# electrical_interface.net
KiCad netlist of a schematic drawn in Altium Designer
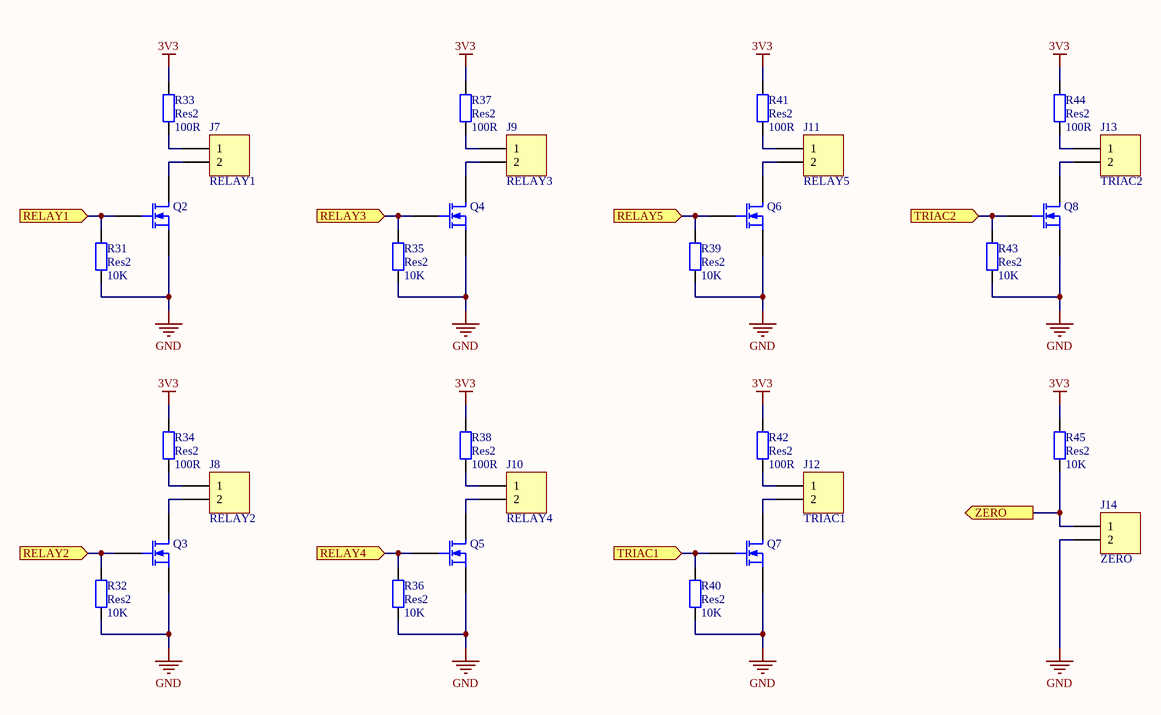
[diagram p0: electrical_interface.SchDoc]

(export (version "E")
  (design (tool "Eeschema 10.0.6"))
  (components
    (comp (ref "J7")
      (value "RELAY1")
      (footprint "Terminal Block")
      (description "Header, 2-Pin")
      (fields (field (name "PUBLISHER") "Altium Limited"))
      (libsource (lib "Miscellaneous Connectors") (part "Header 2"))
    )
    (comp (ref "J8")
      (value "RELAY2")
      (footprint "Terminal Block")
      (description "Header, 2-Pin")
      (fields (field (name "PUBLISHER") "Altium Limited"))
      (libsource (lib "Miscellaneous Connectors") (part "Header 2"))
    )
    (comp (ref "J9")
      (value "RELAY3")
      (footprint "Terminal Block")
      (description "Header, 2-Pin")
      (fields (field (name "PUBLISHER") "Altium Limited"))
      (libsource (lib "Miscellaneous Connectors") (part "Header 2"))
    )
    (comp (ref "J10")
      (value "RELAY4")
      (footprint "Terminal Block")
      (description "Header, 2-Pin")
      (fields (field (name "PUBLISHER") "Altium Limited"))
      (libsource (lib "Miscellaneous Connectors") (part "Header 2"))
    )
    (comp (ref "J11")
      (value "RELAY5")
      (footprint "Terminal Block")
      (description "Header, 2-Pin")
      (fields (field (name "PUBLISHER") "Altium Limited"))
      (libsource (lib "Miscellaneous Connectors") (part "Header 2"))
    )
    (comp (ref "J12")
      (value "TRIAC1")
      (footprint "Terminal Block")
      (description "Header, 2-Pin")
      (fields (field (name "PUBLISHER") "Altium Limited"))
      (libsource (lib "Miscellaneous Connectors") (part "Header 2"))
    )
    (comp (ref "J13")
      (value "TRIAC2")
      (footprint "Terminal Block")
      (description "Header, 2-Pin")
      (fields (field (name "PUBLISHER") "Altium Limited"))
      (libsource (lib "Miscellaneous Connectors") (part "Header 2"))
    )
    (comp (ref "J14")
      (value "ZERO")
      (footprint "Terminal Block")
      (description "Header, 2-Pin")
      (fields (field (name "PUBLISHER") "Altium Limited"))
      (libsource (lib "Miscellaneous Connectors") (part "Header 2"))
    )
    (comp (ref "Q2")
      (value "MOSFET-N")
      (footprint "SOT323")
      (description "N-Channel MOSFET")
      (fields (field (name "PUBLISHER") "Altium Limited"))
      (libsource (lib "Miscellaneous Devices") (part "MOSFET-N"))
    )
    (comp (ref "Q3")
      (value "MOSFET-N")
      (footprint "SOT323")
      (description "N-Channel MOSFET")
      (fields (field (name "PUBLISHER") "Altium Limited"))
      (libsource (lib "Miscellaneous Devices") (part "MOSFET-N"))
    )
    (comp (ref "Q4")
      (value "MOSFET-N")
      (footprint "SOT323")
      (description "N-Channel MOSFET")
      (fields (field (name "PUBLISHER") "Altium Limited"))
      (libsource (lib "Miscellaneous Devices") (part "MOSFET-N"))
    )
    (comp (ref "Q5")
      (value "MOSFET-N")
      (footprint "SOT323")
      (description "N-Channel MOSFET")
      (fields (field (name "PUBLISHER") "Altium Limited"))
      (libsource (lib "Miscellaneous Devices") (part "MOSFET-N"))
    )
    (comp (ref "Q6")
      (value "MOSFET-N")
      (footprint "SOT323")
      (description "N-Channel MOSFET")
      (fields (field (name "PUBLISHER") "Altium Limited"))
      (libsource (lib "Miscellaneous Devices") (part "MOSFET-N"))
    )
    (comp (ref "Q7")
      (value "MOSFET-N")
      (footprint "SOT323")
      (description "N-Channel MOSFET")
      (fields (field (name "PUBLISHER") "Altium Limited"))
      (libsource (lib "Miscellaneous Devices") (part "MOSFET-N"))
    )
    (comp (ref "Q8")
      (value "MOSFET-N")
      (footprint "SOT323")
      (description "N-Channel MOSFET")
      (fields (field (name "PUBLISHER") "Altium Limited"))
      (libsource (lib "Miscellaneous Devices") (part "MOSFET-N"))
    )
    (comp (ref "R31")
      (value "Res2")
      (footprint "0603")
      (description "Resistor")
      (fields (field (name "ALTIUM_VALUE") "10K") (field (name "PUBLISHER") "Altium Limited"))
      (libsource (lib "Miscellaneous Devices") (part "Res2"))
    )
    (comp (ref "R32")
      (value "Res2")
      (footprint "0603")
      (description "Resistor")
      (fields (field (name "ALTIUM_VALUE") "10K") (field (name "PUBLISHER") "Altium Limited"))
      (libsource (lib "Miscellaneous Devices") (part "Res2"))
    )
    (comp (ref "R33")
      (value "Res2")
      (footprint "0603")
      (description "Resistor")
      (fields (field (name "ALTIUM_VALUE") "100R") (field (name "PUBLISHER") "Altium Limited"))
      (libsource (lib "Miscellaneous Devices") (part "Res2"))
    )
    (comp (ref "R34")
      (value "Res2")
      (footprint "0603")
      (description "Resistor")
      (fields (field (name "ALTIUM_VALUE") "100R") (field (name "PUBLISHER") "Altium Limited"))
      (libsource (lib "Miscellaneous Devices") (part "Res2"))
    )
    (comp (ref "R35")
      (value "Res2")
      (footprint "0603")
      (description "Resistor")
      (fields (field (name "ALTIUM_VALUE") "10K") (field (name "PUBLISHER") "Altium Limited"))
      (libsource (lib "Miscellaneous Devices") (part "Res2"))
    )
    (comp (ref "R36")
      (value "Res2")
      (footprint "0603")
      (description "Resistor")
      (fields (field (name "ALTIUM_VALUE") "10K") (field (name "PUBLISHER") "Altium Limited"))
      (libsource (lib "Miscellaneous Devices") (part "Res2"))
    )
    (comp (ref "R37")
      (value "Res2")
      (footprint "0603")
      (description "Resistor")
      (fields (field (name "ALTIUM_VALUE") "100R") (field (name "PUBLISHER") "Altium Limited"))
      (libsource (lib "Miscellaneous Devices") (part "Res2"))
    )
    (comp (ref "R38")
      (value "Res2")
      (footprint "0603")
      (description "Resistor")
      (fields (field (name "ALTIUM_VALUE") "100R") (field (name "PUBLISHER") "Altium Limited"))
      (libsource (lib "Miscellaneous Devices") (part "Res2"))
    )
    (comp (ref "R39")
      (value "Res2")
      (footprint "0603")
      (description "Resistor")
      (fields (field (name "ALTIUM_VALUE") "10K") (field (name "PUBLISHER") "Altium Limited"))
      (libsource (lib "Miscellaneous Devices") (part "Res2"))
    )
    (comp (ref "R40")
      (value "Res2")
      (footprint "0603")
      (description "Resistor")
      (fields (field (name "ALTIUM_VALUE") "10K") (field (name "PUBLISHER") "Altium Limited"))
      (libsource (lib "Miscellaneous Devices") (part "Res2"))
    )
    (comp (ref "R41")
      (value "Res2")
      (footprint "0603")
      (description "Resistor")
      (fields (field (name "ALTIUM_VALUE") "100R") (field (name "PUBLISHER") "Altium Limited"))
      (libsource (lib "Miscellaneous Devices") (part "Res2"))
    )
    (comp (ref "R42")
      (value "Res2")
      (footprint "0603")
      (description "Resistor")
      (fields (field (name "ALTIUM_VALUE") "100R") (field (name "PUBLISHER") "Altium Limited"))
      (libsource (lib "Miscellaneous Devices") (part "Res2"))
    )
    (comp (ref "R43")
      (value "Res2")
      (footprint "0603")
      (description "Resistor")
      (fields (field (name "ALTIUM_VALUE") "10K") (field (name "PUBLISHER") "Altium Limited"))
      (libsource (lib "Miscellaneous Devices") (part "Res2"))
    )
    (comp (ref "R44")
      (value "Res2")
      (footprint "0603")
      (description "Resistor")
      (fields (field (name "ALTIUM_VALUE") "100R") (field (name "PUBLISHER") "Altium Limited"))
      (libsource (lib "Miscellaneous Devices") (part "Res2"))
    )
    (comp (ref "R45")
      (value "Res2")
      (footprint "0603")
      (description "Resistor")
      (fields (field (name "ALTIUM_VALUE") "10K") (field (name "PUBLISHER") "Altium Limited"))
      (libsource (lib "Miscellaneous Devices") (part "Res2"))
    )
  )
  (nets
    (net (code "1") (name "/RELAY1") (class "Default")
      (node (ref "Q2") (pin "2") (pinfunction "G_2") (pintype "passive"))
      (node (ref "R31") (pin "2") (pinfunction "2_2") (pintype "passive"))
    )
    (net (code "2") (name "/RELAY2") (class "Default")
      (node (ref "Q3") (pin "2") (pinfunction "G_2") (pintype "passive"))
      (node (ref "R32") (pin "2") (pinfunction "2_2") (pintype "passive"))
    )
    (net (code "3") (name "/RELAY3") (class "Default")
      (node (ref "Q4") (pin "2") (pinfunction "G_2") (pintype "passive"))
      (node (ref "R35") (pin "2") (pinfunction "2_2") (pintype "passive"))
    )
    (net (code "4") (name "/RELAY4") (class "Default")
      (node (ref "Q5") (pin "2") (pinfunction "G_2") (pintype "passive"))
      (node (ref "R36") (pin "2") (pinfunction "2_2") (pintype "passive"))
    )
    (net (code "5") (name "/RELAY5") (class "Default")
      (node (ref "Q6") (pin "2") (pinfunction "G_2") (pintype "passive"))
      (node (ref "R39") (pin "2") (pinfunction "2_2") (pintype "passive"))
    )
    (net (code "6") (name "/TRIAC1") (class "Default")
      (node (ref "Q7") (pin "2") (pinfunction "G_2") (pintype "passive"))
      (node (ref "R40") (pin "2") (pinfunction "2_2") (pintype "passive"))
    )
    (net (code "7") (name "/TRIAC2") (class "Default")
      (node (ref "Q8") (pin "2") (pinfunction "G_2") (pintype "passive"))
      (node (ref "R43") (pin "2") (pinfunction "2_2") (pintype "passive"))
    )
    (net (code "8") (name "/ZERO") (class "Default")
      (node (ref "J14") (pin "1") (pinfunction "1_1") (pintype "passive"))
      (node (ref "R45") (pin "1") (pinfunction "1_1") (pintype "passive"))
    )
    (net (code "9") (name "3V3") (class "Default")
      (node (ref "R33") (pin "2") (pinfunction "2_2") (pintype "passive"))
      (node (ref "R34") (pin "2") (pinfunction "2_2") (pintype "passive"))
      (node (ref "R37") (pin "2") (pinfunction "2_2") (pintype "passive"))
      (node (ref "R38") (pin "2") (pinfunction "2_2") (pintype "passive"))
      (node (ref "R41") (pin "2") (pinfunction "2_2") (pintype "passive"))
      (node (ref "R42") (pin "2") (pinfunction "2_2") (pintype "passive"))
      (node (ref "R44") (pin "2") (pinfunction "2_2") (pintype "passive"))
      (node (ref "R45") (pin "2") (pinfunction "2_2") (pintype "passive"))
    )
    (net (code "10") (name "GND") (class "Default")
      (node (ref "J14") (pin "2") (pinfunction "2_2") (pintype "passive"))
      (node (ref "Q2") (pin "3") (pinfunction "S_3") (pintype "passive"))
      (node (ref "Q3") (pin "3") (pinfunction "S_3") (pintype "passive"))
      (node (ref "Q4") (pin "3") (pinfunction "S_3") (pintype "passive"))
      (node (ref "Q5") (pin "3") (pinfunction "S_3") (pintype "passive"))
      (node (ref "Q6") (pin "3") (pinfunction "S_3") (pintype "passive"))
      (node (ref "Q7") (pin "3") (pinfunction "S_3") (pintype "passive"))
      (node (ref "Q8") (pin "3") (pinfunction "S_3") (pintype "passive"))
      (node (ref "R31") (pin "1") (pinfunction "1_1") (pintype "passive"))
      (node (ref "R32") (pin "1") (pinfunction "1_1") (pintype "passive"))
      (node (ref "R35") (pin "1") (pinfunction "1_1") (pintype "passive"))
      (node (ref "R36") (pin "1") (pinfunction "1_1") (pintype "passive"))
      (node (ref "R39") (pin "1") (pinfunction "1_1") (pintype "passive"))
      (node (ref "R40") (pin "1") (pinfunction "1_1") (pintype "passive"))
      (node (ref "R43") (pin "1") (pinfunction "1_1") (pintype "passive"))
    )
    (net (code "11") (name "Net-(J7-Pad1)") (class "Default")
      (node (ref "J7") (pin "1") (pinfunction "1_1") (pintype "passive"))
      (node (ref "R33") (pin "1") (pinfunction "1_1") (pintype "passive"))
    )
    (net (code "12") (name "Net-(J8-Pad1)") (class "Default")
      (node (ref "J8") (pin "1") (pinfunction "1_1") (pintype "passive"))
      (node (ref "R34") (pin "1") (pinfunction "1_1") (pintype "passive"))
    )
    (net (code "13") (name "Net-(J9-Pad1)") (class "Default")
      (node (ref "J9") (pin "1") (pinfunction "1_1") (pintype "passive"))
      (node (ref "R37") (pin "1") (pinfunction "1_1") (pintype "passive"))
    )
    (net (code "14") (name "Net-(J10-Pad1)") (class "Default")
      (node (ref "J10") (pin "1") (pinfunction "1_1") (pintype "passive"))
      (node (ref "R38") (pin "1") (pinfunction "1_1") (pintype "passive"))
    )
    (net (code "15") (name "Net-(J11-Pad1)") (class "Default")
      (node (ref "J11") (pin "1") (pinfunction "1_1") (pintype "passive"))
      (node (ref "R41") (pin "1") (pinfunction "1_1") (pintype "passive"))
    )
    (net (code "16") (name "Net-(J12-Pad1)") (class "Default")
      (node (ref "J12") (pin "1") (pinfunction "1_1") (pintype "passive"))
      (node (ref "R42") (pin "1") (pinfunction "1_1") (pintype "passive"))
    )
    (net (code "17") (name "Net-(J13-Pad1)") (class "Default")
      (node (ref "J13") (pin "1") (pinfunction "1_1") (pintype "passive"))
      (node (ref "R44") (pin "1") (pinfunction "1_1") (pintype "passive"))
    )
    (net (code "18") (name "Net-(Q2-D)") (class "Default")
      (node (ref "J7") (pin "2") (pinfunction "2_2") (pintype "passive"))
      (node (ref "Q2") (pin "1") (pinfunction "D_1") (pintype "passive"))
    )
    (net (code "19") (name "Net-(Q3-D)") (class "Default")
      (node (ref "J8") (pin "2") (pinfunction "2_2") (pintype "passive"))
      (node (ref "Q3") (pin "1") (pinfunction "D_1") (pintype "passive"))
    )
    (net (code "20") (name "Net-(Q4-D)") (class "Default")
      (node (ref "J9") (pin "2") (pinfunction "2_2") (pintype "passive"))
      (node (ref "Q4") (pin "1") (pinfunction "D_1") (pintype "passive"))
    )
    (net (code "21") (name "Net-(Q5-D)") (class "Default")
      (node (ref "J10") (pin "2") (pinfunction "2_2") (pintype "passive"))
      (node (ref "Q5") (pin "1") (pinfunction "D_1") (pintype "passive"))
    )
    (net (code "22") (name "Net-(Q6-D)") (class "Default")
      (node (ref "J11") (pin "2") (pinfunction "2_2") (pintype "passive"))
      (node (ref "Q6") (pin "1") (pinfunction "D_1") (pintype "passive"))
    )
    (net (code "23") (name "Net-(Q7-D)") (class "Default")
      (node (ref "J12") (pin "2") (pinfunction "2_2") (pintype "passive"))
      (node (ref "Q7") (pin "1") (pinfunction "D_1") (pintype "passive"))
    )
    (net (code "24") (name "Net-(Q8-D)") (class "Default")
      (node (ref "J13") (pin "2") (pinfunction "2_2") (pintype "passive"))
      (node (ref "Q8") (pin "1") (pinfunction "D_1") (pintype "passive"))
    )
  )
)
